# GEARDRONE_LITE.net
KiCad netlist of a schematic drawn in Altium Designer
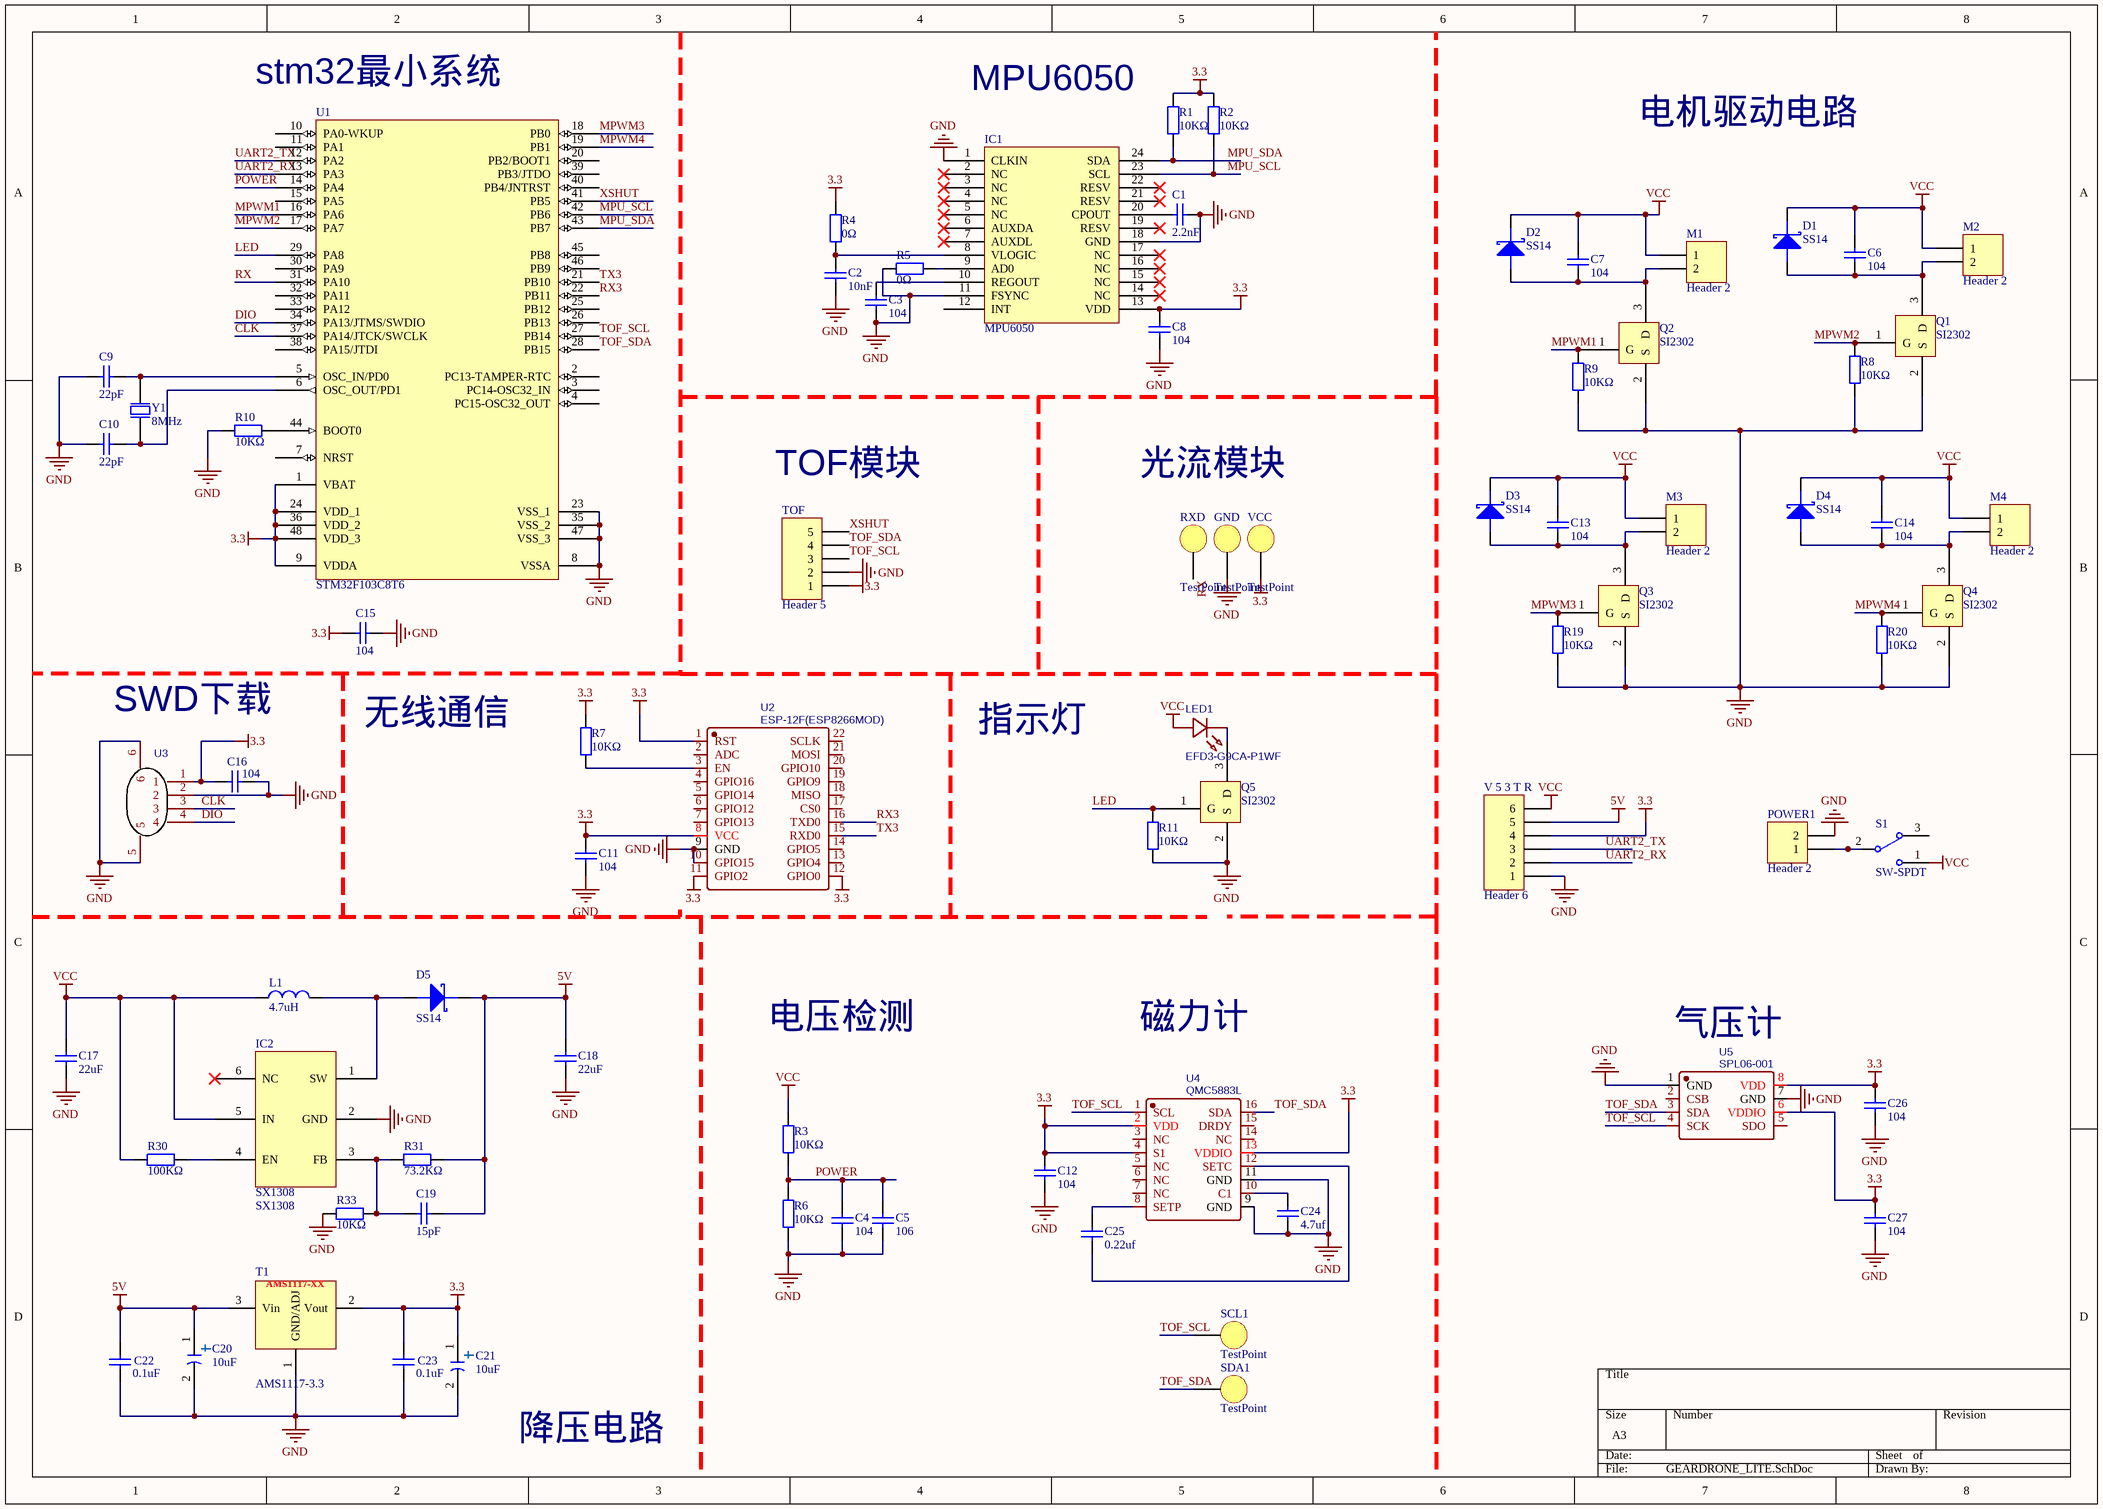
[diagram p0: GEARDRONE_LITE.SchDoc]

(export (version "E")
  (design (tool "Eeschema 10.0.6"))
  (components
    (comp (ref "C1")
      (value "2.2nF")
      (footprint "C0603")
      (description "Polarized Capacitor (Radial)")
      (fields (field (name "Comment") "2.2nf") (field (name "PUBLISHER") "Altium Limited"))
      (libsource (lib "电容") (part "Cap Chip 0603"))
    )
    (comp (ref "C2")
      (value "10nF")
      (footprint "C0603")
      (description "Polarized Capacitor (Radial)")
      (fields (field (name "Comment") "10nf") (field (name "PUBLISHER") "Altium Limited"))
      (libsource (lib "电容") (part "Cap Chip 0603"))
    )
    (comp (ref "C3")
      (value "104")
      (footprint "C0603")
      (description "Polarized Capacitor (Radial)")
      (fields (field (name "PUBLISHER") "Altium Limited"))
      (libsource (lib "电容") (part "Cap Chip 0603"))
    )
    (comp (ref "C4")
      (value "104")
      (footprint "C0603")
      (description "Polarized Capacitor (Radial)")
      (fields (field (name "PUBLISHER") "Altium Limited"))
      (libsource (lib "电容") (part "Cap Chip 0603"))
    )
    (comp (ref "C5")
      (value "106")
      (footprint "C0603")
      (description "Polarized Capacitor (Radial)")
      (fields (field (name "PUBLISHER") "Altium Limited"))
      (libsource (lib "电容") (part "Cap Chip 0603"))
    )
    (comp (ref "C6")
      (value "104")
      (footprint "C0603")
      (description "Polarized Capacitor (Radial)")
      (fields (field (name "PUBLISHER") "Altium Limited"))
      (libsource (lib "电容") (part "Cap Chip 0603"))
    )
    (comp (ref "C7")
      (value "104")
      (footprint "C0603")
      (description "Polarized Capacitor (Radial)")
      (fields (field (name "PUBLISHER") "Altium Limited"))
      (libsource (lib "电容") (part "Cap Chip 0603"))
    )
    (comp (ref "C8")
      (value "104")
      (footprint "C0603")
      (description "Polarized Capacitor (Radial)")
      (fields (field (name "PUBLISHER") "Altium Limited"))
      (libsource (lib "电容") (part "Cap Chip 0603"))
    )
    (comp (ref "C9")
      (value "22pF")
      (footprint "C0603")
      (description "Polarized Capacitor (Radial)")
      (fields (field (name "Comment") "20pf") (field (name "PUBLISHER") "Altium Limited"))
      (libsource (lib "电容") (part "Cap Chip 0805"))
    )
    (comp (ref "C10")
      (value "22pF")
      (footprint "C0603")
      (description "Polarized Capacitor (Radial)")
      (fields (field (name "PUBLISHER") "Altium Limited"))
      (libsource (lib "电容") (part "Cap Chip 0805"))
    )
    (comp (ref "C11")
      (value "104")
      (footprint "0603_C")
      (description "Polarized Capacitor (Radial)")
      (fields (field (name "PUBLISHER") "Altium Limited"))
      (libsource (lib "电容") (part "Cap Chip 0603"))
    )
    (comp (ref "C12")
      (value "104")
      (footprint "0603_C")
      (description "Polarized Capacitor (Radial)")
      (fields (field (name "PUBLISHER") "Altium Limited"))
      (libsource (lib "电容") (part "Cap Chip 0603"))
    )
    (comp (ref "C13")
      (value "104")
      (footprint "C0603")
      (description "Polarized Capacitor (Radial)")
      (fields (field (name "PUBLISHER") "Altium Limited"))
      (libsource (lib "电容") (part "Cap Chip 0603"))
    )
    (comp (ref "C14")
      (value "104")
      (footprint "C0603")
      (description "Polarized Capacitor (Radial)")
      (fields (field (name "PUBLISHER") "Altium Limited"))
      (libsource (lib "电容") (part "Cap Chip 0603"))
    )
    (comp (ref "C15")
      (value "104")
      (footprint "C0603")
      (description "Polarized Capacitor (Radial)")
      (fields (field (name "PUBLISHER") "Altium Limited"))
      (libsource (lib "电容") (part "Cap Chip 0603"))
    )
    (comp (ref "C16")
      (value "104")
      (footprint "C0603")
      (description "Polarized Capacitor (Radial)")
      (fields (field (name "PUBLISHER") "Altium Limited"))
      (libsource (lib "电容") (part "Cap Chip 0603"))
    )
    (comp (ref "C17")
      (value "22uF")
      (footprint "C0603")
      (description "Polarized Capacitor (Radial)")
      (fields (field (name "Comment") "22uf") (field (name "PUBLISHER") "Altium Limited"))
      (libsource (lib "电容") (part "Cap Chip 0603"))
    )
    (comp (ref "C18")
      (value "22uF")
      (footprint "C0603")
      (description "Polarized Capacitor (Radial)")
      (fields (field (name "Comment") "22uf") (field (name "PUBLISHER") "Altium Limited"))
      (libsource (lib "电容") (part "Cap Chip 0603"))
    )
    (comp (ref "C19")
      (value "15pF")
      (footprint "C0603")
      (description "Polarized Capacitor (Radial)")
      (fields (field (name "Comment") "15pf") (field (name "PUBLISHER") "Altium Limited"))
      (libsource (lib "电容") (part "Cap Chip 0603"))
    )
    (comp (ref "C20")
      (value "ECAP")
      (footprint "TAN-A-3216")
      (fields (field (name "ALTIUM_UNNAMED_1") "10uF"))
      (libsource (lib "mySchlib") (part "ECAP"))
    )
    (comp (ref "C21")
      (value "ECAP")
      (footprint "TAN-A-3216")
      (fields (field (name "ALTIUM_UNNAMED_1") "10uF"))
      (libsource (lib "mySchlib") (part "ECAP"))
    )
    (comp (ref "C22")
      (value "0.1uF")
      (footprint "C0603")
      (description "Polarized Capacitor (Radial)")
      (fields (field (name "Comment") "0.1uf") (field (name "PUBLISHER") "Altium Limited"))
      (libsource (lib "电容") (part "Cap Chip 0603"))
    )
    (comp (ref "C23")
      (value "0.1uF")
      (footprint "C0603")
      (description "Polarized Capacitor (Radial)")
      (fields (field (name "Comment") "0.1uf") (field (name "PUBLISHER") "Altium Limited"))
      (libsource (lib "电容") (part "Cap Chip 0603"))
    )
    (comp (ref "C24")
      (value "4.7uf")
      (footprint "0603_C")
      (description "Polarized Capacitor (Radial)")
      (fields (field (name "PUBLISHER") "Altium Limited"))
      (libsource (lib "电容") (part "Cap Chip 0603"))
    )
    (comp (ref "C25")
      (value "0.22uf")
      (footprint "0603_C")
      (description "Polarized Capacitor (Radial)")
      (fields (field (name "PUBLISHER") "Altium Limited"))
      (libsource (lib "电容") (part "Cap Chip 0603"))
    )
    (comp (ref "C26")
      (value "104")
      (footprint "0603_C")
      (description "Polarized Capacitor (Radial)")
      (fields (field (name "PUBLISHER") "Altium Limited"))
      (libsource (lib "电容") (part "Cap Chip 0603"))
    )
    (comp (ref "C27")
      (value "104")
      (footprint "0603_C")
      (description "Polarized Capacitor (Radial)")
      (fields (field (name "PUBLISHER") "Altium Limited"))
      (libsource (lib "电容") (part "Cap Chip 0603"))
    )
    (comp (ref "D1") (value "SS14") (footprint "SOD-323") (libsource (lib "二极管 三极管 MOS") (part "DIODE-TVS")))
    (comp (ref "D2") (value "SS14") (footprint "SOD-323") (libsource (lib "二极管 三极管 MOS") (part "DIODE-TVS")))
    (comp (ref "D3") (value "SS14") (footprint "SOD-323") (libsource (lib "二极管 三极管 MOS") (part "DIODE-TVS")))
    (comp (ref "D4") (value "SS14") (footprint "SOD-323") (libsource (lib "二极管 三极管 MOS") (part "DIODE-TVS")))
    (comp (ref "D5") (value "SS14") (footprint "SOD-323") (libsource (lib "二极管 三极管 MOS") (part "DIODE-TVS")))
    (comp (ref "GND")
      (value "TestPoint")
      (footprint "TestPoint")
      (libsource (lib "CQL_SchLib") (part "TestPoint"))
    )
    (comp (ref "IC1")
      (value "MPU6050")
      (footprint "LC-QFN-24_4x4x05P")
      (description "三轴陀螺仪")
      (libsource (lib "模块") (part "MPU6050"))
    )
    (comp (ref "IC2") (value "SX1308") (footprint "LC-SOT-23-6") (libsource (lib "Schlib1") (part "SX1308")))
    (comp (ref "L1")
      (value "4.7uH")
      (footprint "CD43NP")
      (description "Inductor")
      (fields (field (name "PUBLISHER") "Altium Limited"))
      (libsource (lib "电感磁珠共轭圈") (part "Inductor Chip"))
    )
    (comp (ref "LED1")
      (value "EFD3-G9CA-P1WF")
      (footprint "LED3528")
      (fields (field (name "BOM_SUPPLIER PART") "C507038") (field (name "CONTRIBUTOR") "LCSC"))
      (libsource (lib "altium-import") (part "root_2_EFD3-G9CA-P1WF_"))
    )
    (comp (ref "M1")
      (value "Header 2")
      (footprint "HDR1X2")
      (description "Header, 2-Pin")
      (fields (field (name "PUBLISHER") "Altium Limited"))
      (libsource (lib "The BeatlesIntegratedLibrary") (part "Header 2"))
    )
    (comp (ref "M2")
      (value "Header 2")
      (footprint "HDR1X2")
      (description "Header, 2-Pin")
      (fields (field (name "PUBLISHER") "Altium Limited"))
      (libsource (lib "The BeatlesIntegratedLibrary") (part "Header 2"))
    )
    (comp (ref "M3")
      (value "Header 2")
      (footprint "HDR1X2")
      (description "Header, 2-Pin")
      (fields (field (name "PUBLISHER") "Altium Limited"))
      (libsource (lib "The BeatlesIntegratedLibrary") (part "Header 2"))
    )
    (comp (ref "M4")
      (value "Header 2")
      (footprint "HDR1X2")
      (description "Header, 2-Pin")
      (fields (field (name "PUBLISHER") "Altium Limited"))
      (libsource (lib "The BeatlesIntegratedLibrary") (part "Header 2"))
    )
    (comp (ref "POWER1")
      (value "Header 2")
      (footprint "HDR1X2")
      (description "Header, 2-Pin")
      (fields (field (name "PUBLISHER") "Altium Limited"))
      (libsource (lib "") (part "Header 2_1"))
    )
    (comp (ref "Q1")
      (value "SI2302")
      (footprint "LC-SOT-23(SOT-23-3)")
      (libsource (lib "SI2302") (part "HANDSOME-SI2302-N"))
    )
    (comp (ref "Q2")
      (value "SI2302")
      (footprint "LC-SOT-23(SOT-23-3)")
      (libsource (lib "SI2302") (part "HANDSOME-SI2302-N"))
    )
    (comp (ref "Q3")
      (value "SI2302")
      (footprint "LC-SOT-23(SOT-23-3)")
      (libsource (lib "SI2302") (part "HANDSOME-SI2302-N"))
    )
    (comp (ref "Q4")
      (value "SI2302")
      (footprint "LC-SOT-23(SOT-23-3)")
      (libsource (lib "SI2302") (part "HANDSOME-SI2302-N"))
    )
    (comp (ref "Q5")
      (value "SI2302")
      (footprint "LC-SOT-23(SOT-23-3)")
      (libsource (lib "SI2302") (part "HANDSOME-SI2302-N"))
    )
    (comp (ref "R1")
      (value "10KΩ")
      (footprint "R0603")
      (description "Resistor")
      (fields (field (name "Comment") "10k") (field (name "PUBLISHER") "Altium Limited"))
      (libsource (lib "电阻") (part "Resistor Chip 0805"))
    )
    (comp (ref "R2")
      (value "10KΩ")
      (footprint "R0603")
      (description "Resistor")
      (fields (field (name "Comment") "10k") (field (name "PUBLISHER") "Altium Limited"))
      (libsource (lib "电阻") (part "Resistor Chip 0805"))
    )
    (comp (ref "R3")
      (value "10KΩ")
      (footprint "R0603")
      (description "Resistor")
      (fields (field (name "Comment") "10k") (field (name "PUBLISHER") "Altium Limited"))
      (libsource (lib "电阻") (part "Resistor Chip 0805"))
    )
    (comp (ref "R4")
      (value "0Ω")
      (footprint "R0603")
      (description "Resistor")
      (fields (field (name "Comment") "0") (field (name "PUBLISHER") "Altium Limited"))
      (libsource (lib "") (part "Resistor Chip 0805_3"))
    )
    (comp (ref "R5")
      (value "0Ω")
      (footprint "R0603")
      (description "Resistor")
      (fields (field (name "Comment") "0") (field (name "PUBLISHER") "Altium Limited"))
      (libsource (lib "") (part "Resistor Chip 0805_1"))
    )
    (comp (ref "R6")
      (value "10KΩ")
      (footprint "R0603")
      (description "Resistor")
      (fields (field (name "Comment") "10k") (field (name "PUBLISHER") "Altium Limited"))
      (libsource (lib "电阻") (part "Resistor Chip 0805"))
    )
    (comp (ref "R7")
      (value "10KΩ")
      (footprint "0603_R")
      (description "Resistor")
      (fields (field (name "Comment") "10k") (field (name "PUBLISHER") "Altium Limited"))
      (libsource (lib "电阻") (part "Resistor Chip 0805"))
    )
    (comp (ref "R8")
      (value "10KΩ")
      (footprint "R0603")
      (description "Resistor")
      (fields (field (name "Comment") "10k") (field (name "PUBLISHER") "Altium Limited"))
      (libsource (lib "电阻") (part "Resistor Chip 0805"))
    )
    (comp (ref "R9")
      (value "10KΩ")
      (footprint "R0603")
      (description "Resistor")
      (fields (field (name "Comment") "10k") (field (name "PUBLISHER") "Altium Limited"))
      (libsource (lib "") (part "Resistor Chip 0805_3"))
    )
    (comp (ref "R10")
      (value "10KΩ")
      (footprint "R0603")
      (description "Resistor")
      (fields (field (name "Comment") "10kΩ") (field (name "PUBLISHER") "Altium Limited"))
      (libsource (lib "") (part "Resistor Chip 0805_1"))
    )
    (comp (ref "R11")
      (value "10KΩ")
      (footprint "0603_R")
      (description "Resistor")
      (fields (field (name "Comment") "10k") (field (name "PUBLISHER") "Altium Limited"))
      (libsource (lib "") (part "Resistor Chip 0805_3"))
    )
    (comp (ref "R19")
      (value "10KΩ")
      (footprint "R0603")
      (description "Resistor")
      (fields (field (name "Comment") "10k") (field (name "PUBLISHER") "Altium Limited"))
      (libsource (lib "电阻") (part "Resistor Chip 0805"))
    )
    (comp (ref "R20")
      (value "10KΩ")
      (footprint "R0603")
      (description "Resistor")
      (fields (field (name "Comment") "10k") (field (name "PUBLISHER") "Altium Limited"))
      (libsource (lib "电阻") (part "Resistor Chip 0805"))
    )
    (comp (ref "R30")
      (value "100KΩ")
      (footprint "R0603")
      (description "Resistor")
      (fields (field (name "Comment") "100k") (field (name "PUBLISHER") "Altium Limited"))
      (libsource (lib "") (part "Resistor Chip 0805_1"))
    )
    (comp (ref "R31")
      (value "73.2KΩ")
      (footprint "R0603")
      (description "Resistor")
      (fields (field (name "Comment") "73.2k") (field (name "PUBLISHER") "Altium Limited"))
      (libsource (lib "") (part "Resistor Chip 0805_1"))
    )
    (comp (ref "R33")
      (value "10KΩ")
      (footprint "R0603")
      (description "Resistor")
      (fields (field (name "Comment") "10k") (field (name "PUBLISHER") "Altium Limited"))
      (libsource (lib "") (part "Resistor Chip 0805_2"))
    )
    (comp (ref "RXD")
      (value "TestPoint")
      (footprint "TestPoint")
      (libsource (lib "CQL_SchLib") (part "TestPoint"))
    )
    (comp (ref "S1")
      (value "SW-SPDT")
      (footprint "SW-TH_SS-12D10L5")
      (description "SPDT Subminiature Toggle Switch, Right Angle Mounting, Vertical Actuation")
      (fields (field (name "PUBLISHER") "Altium Limited"))
      (libsource (lib "开关按键器件") (part "SW-SPDT"))
    )
    (comp (ref "SCL1")
      (value "TestPoint")
      (footprint "TestPoint")
      (libsource (lib "CQL_SchLib") (part "TestPoint"))
    )
    (comp (ref "SDA1")
      (value "TestPoint")
      (footprint "TestPoint")
      (libsource (lib "CQL_SchLib") (part "TestPoint"))
    )
    (comp (ref "T1")
      (value "AMS1117-3.3")
      (footprint "SOT230P700X180-4N-LM2940")
      (description "AMS   800mA LOW DROPOUT VOLTAGE REGULATOR")
      (libsource (lib "电源ICs") (part "AMS1117-XX"))
    )
    (comp (ref "TOF")
      (value "Header 5")
      (footprint "HDR1X5")
      (description "Header, 5-Pin")
      (fields (field (name "PUBLISHER") "Altium Limited"))
      (libsource (lib "Miscellaneous Connectors") (part "Header 5"))
    )
    (comp (ref "U1")
      (value "STM32F103C8T6")
      (footprint "LC-LQFP-48_7x7x05P")
      (description "STM32 ARM-based 32-bit MCU with 64 Kbytes Flash, 48-pin LQFP, Industrial Temperature")
      (fields (field (name "PUBLISHER") "*"))
      (libsource (lib "ST MCU元件库") (part "STM32F103C8T6"))
    )
    (comp (ref "U2")
      (value "ESP-12F(ESP8266MOD)")
      (footprint "WIFIM-SMD_ESP-12F-ESP8266MOD")
      (fields (field (name "BOM_SUPPLIER PART") "C82891"))
      (libsource (lib "altium-import") (part "root_0_ESP-12F(ESP8266MOD)_"))
    )
    (comp (ref "U3")
      (value "SM04B-GHS-TB(LF)(SN)")
      (footprint "CONN-SMD_4P-P1.25_SM04B-GHS-TB-LF-SN")
      (fields (field (name "BOM_SUPPLIER PART") "C189895") (field (name "CONTRIBUTOR") "LCSC"))
      (libsource (lib "Y1") (part "SM04B-GHS-TB(LF)(SN)"))
    )
    (comp (ref "U4")
      (value "QMC5883L")
      (footprint "LPCC-16_L3.0-W3.0-P0.50-BL")
      (fields
        (field (name "BOM_SUPPLIER PART") "C2859540")
        (field (name "BOM_MANUFACTURER PART") "HMC5883L")
        (field (name "CONTRIBUTOR") "LCSC")
      )
      (libsource (lib "altium-import") (part "root_0_HMC5883L_"))
    )
    (comp (ref "U5")
      (value "SPL06-001")
      (footprint "SENSOR-SMD_SPL06-001")
      (fields (field (name "BOM_SUPPLIER PART") "C2684428") (field (name "CONTRIBUTOR") "LCSC"))
      (libsource (lib "altium-import") (part "root_0_SPL06-001_"))
    )
    (comp (ref "V 5 3 T R")
      (value "Header 6")
      (footprint "HDR1X6")
      (description "Header, 6-Pin")
      (fields (field (name "PUBLISHER") "Altium Limited"))
      (libsource (lib "Miscellaneous Connectors") (part "Header 6"))
    )
    (comp (ref "VCC")
      (value "TestPoint")
      (footprint "TestPoint")
      (libsource (lib "CQL_SchLib") (part "TestPoint"))
    )
    (comp (ref "Y1")
      (value "5032")
      (footprint "SMD5032-2")
      (description "Crystal Oscillator")
      (fields (field (name "FREQUENCY") "8MHz") (field (name "PUBLISHER") "Altium Limited"))
      (libsource (lib "蜂鸣器 咪头 保险丝 电池 晶振") (part "XTAL"))
    )
  )
  (nets
    (net (code "1") (name "/CLK") (class "Default")
      (node (ref "U1") (pin "37") (pinfunction "PA14/JTCK/SWCLK_37") (pintype "bidirectional"))
      (node (ref "U3") (pin "3") (pinfunction "3_3") (pintype "passive"))
    )
    (net (code "2") (name "/DIO") (class "Default")
      (node (ref "U1") (pin "34") (pinfunction "PA13/JTMS/SWDIO_34") (pintype "bidirectional"))
      (node (ref "U3") (pin "4") (pinfunction "4_4") (pintype "passive"))
    )
    (net (code "3") (name "/LED") (class "Default")
      (node (ref "Q5") (pin "1") (pinfunction "G_1") (pintype "passive"))
      (node (ref "R11") (pin "2") (pinfunction "2_2") (pintype "passive"))
      (node (ref "U1") (pin "29") (pinfunction "PA8_29") (pintype "bidirectional"))
    )
    (net (code "4") (name "/MPU_SCL") (class "Default")
      (node (ref "IC1") (pin "23") (pinfunction "SCL_23") (pintype "passive"))
      (node (ref "R2") (pin "2") (pinfunction "2_2") (pintype "passive"))
      (node (ref "U1") (pin "42") (pinfunction "PB6_42") (pintype "bidirectional"))
    )
    (net (code "5") (name "/MPU_SDA") (class "Default")
      (node (ref "IC1") (pin "24") (pinfunction "SDA_24") (pintype "passive"))
      (node (ref "R1") (pin "2") (pinfunction "2_2") (pintype "passive"))
      (node (ref "U1") (pin "43") (pinfunction "PB7_43") (pintype "bidirectional"))
    )
    (net (code "6") (name "/MPWM1") (class "Default")
      (node (ref "Q2") (pin "1") (pinfunction "G_1") (pintype "passive"))
      (node (ref "R9") (pin "2") (pinfunction "2_2") (pintype "passive"))
      (node (ref "U1") (pin "16") (pinfunction "PA6_16") (pintype "bidirectional"))
    )
    (net (code "7") (name "/MPWM2") (class "Default")
      (node (ref "Q1") (pin "1") (pinfunction "G_1") (pintype "passive"))
      (node (ref "R8") (pin "1") (pinfunction "1_1") (pintype "passive"))
      (node (ref "U1") (pin "17") (pinfunction "PA7_17") (pintype "bidirectional"))
    )
    (net (code "8") (name "/MPWM3") (class "Default")
      (node (ref "Q3") (pin "1") (pinfunction "G_1") (pintype "passive"))
      (node (ref "R19") (pin "1") (pinfunction "1_1") (pintype "passive"))
      (node (ref "U1") (pin "18") (pinfunction "PB0_18") (pintype "bidirectional"))
    )
    (net (code "9") (name "/MPWM4") (class "Default")
      (node (ref "Q4") (pin "1") (pinfunction "G_1") (pintype "passive"))
      (node (ref "R20") (pin "1") (pinfunction "1_1") (pintype "passive"))
      (node (ref "U1") (pin "19") (pinfunction "PB1_19") (pintype "bidirectional"))
    )
    (net (code "10") (name "/POWER") (class "Default")
      (node (ref "C4") (pin "1") (pinfunction "1_1") (pintype "passive"))
      (node (ref "C5") (pin "1") (pinfunction "1_1") (pintype "passive"))
      (node (ref "R3") (pin "2") (pinfunction "2_2") (pintype "passive"))
      (node (ref "R6") (pin "1") (pinfunction "1_1") (pintype "passive"))
      (node (ref "U1") (pin "14") (pinfunction "PA4_14") (pintype "bidirectional"))
    )
    (net (code "11") (name "/RX") (class "Default")
      (node (ref "RXD") (pin "1") (pinfunction "TestPoint_1") (pintype "passive"))
      (node (ref "U1") (pin "31") (pinfunction "PA10_31") (pintype "bidirectional"))
    )
    (net (code "12") (name "/RX3") (class "Default")
      (node (ref "U1") (pin "22") (pinfunction "PB11_22") (pintype "bidirectional"))
      (node (ref "U2") (pin "16") (pinfunction "TXD0_16") (pintype "passive"))
    )
    (net (code "13") (name "/TOF_SCL") (class "Default")
      (node (ref "SCL1") (pin "1") (pinfunction "TestPoint_1") (pintype "passive"))
      (node (ref "TOF") (pin "3") (pinfunction "3_3") (pintype "passive"))
      (node (ref "U1") (pin "27") (pinfunction "PB14_27") (pintype "bidirectional"))
      (node (ref "U4") (pin "1") (pinfunction "SCL_1") (pintype "passive"))
      (node (ref "U5") (pin "4") (pinfunction "SCK_4") (pintype "passive"))
    )
    (net (code "14") (name "/TOF_SDA") (class "Default")
      (node (ref "SDA1") (pin "1") (pinfunction "TestPoint_1") (pintype "passive"))
      (node (ref "TOF") (pin "4") (pinfunction "4_4") (pintype "passive"))
      (node (ref "U1") (pin "28") (pinfunction "PB15_28") (pintype "bidirectional"))
      (node (ref "U4") (pin "16") (pinfunction "SDA_16") (pintype "passive"))
      (node (ref "U5") (pin "3") (pinfunction "SDA_3") (pintype "passive"))
    )
    (net (code "15") (name "/TX3") (class "Default")
      (node (ref "U1") (pin "21") (pinfunction "PB10_21") (pintype "bidirectional"))
      (node (ref "U2") (pin "15") (pinfunction "RXD0_15") (pintype "passive"))
    )
    (net (code "16") (name "/UART2_RX") (class "Default")
      (node (ref "U1") (pin "13") (pinfunction "PA3_13") (pintype "bidirectional"))
      (node (ref "V 5 3 T R") (pin "2") (pinfunction "2_2") (pintype "passive"))
    )
    (net (code "17") (name "/UART2_TX") (class "Default")
      (node (ref "U1") (pin "12") (pinfunction "PA2_12") (pintype "bidirectional"))
      (node (ref "V 5 3 T R") (pin "3") (pinfunction "3_3") (pintype "passive"))
    )
    (net (code "18") (name "/XSHUT") (class "Default")
      (node (ref "TOF") (pin "5") (pinfunction "5_5") (pintype "passive"))
      (node (ref "U1") (pin "41") (pinfunction "PB5_41") (pintype "bidirectional"))
    )
    (net (code "19") (name "3.3") (class "Default")
      (node (ref "C11") (pin "1") (pinfunction "1_1") (pintype "passive"))
      (node (ref "C12") (pin "1") (pinfunction "1_1") (pintype "passive"))
      (node (ref "C15") (pin "2") (pinfunction "2_2") (pintype "passive"))
      (node (ref "C16") (pin "2") (pinfunction "2_2") (pintype "passive"))
      (node (ref "C21") (pin "1") (pinfunction "1_1") (pintype "passive"))
      (node (ref "C23") (pin "2") (pinfunction "2_2") (pintype "passive"))
      (node (ref "C26") (pin "1") (pinfunction "1_1") (pintype "passive"))
      (node (ref "C27") (pin "1") (pinfunction "1_1") (pintype "passive"))
      (node (ref "C8") (pin "1") (pinfunction "1_1") (pintype "passive"))
      (node (ref "IC1") (pin "13") (pinfunction "VDD_13") (pintype "passive"))
      (node (ref "R1") (pin "1") (pinfunction "1_1") (pintype "passive"))
      (node (ref "R2") (pin "1") (pinfunction "1_1") (pintype "passive"))
      (node (ref "R4") (pin "2") (pinfunction "2_2") (pintype "passive"))
      (node (ref "R7") (pin "1") (pinfunction "1_1") (pintype "passive"))
      (node (ref "T1") (pin "2") (pinfunction "Vout_2") (pintype "passive"))
      (node (ref "TOF") (pin "1") (pinfunction "1_1") (pintype "passive"))
      (node (ref "U1") (pin "1") (pinfunction "VBAT_1") (pintype "power_in"))
      (node (ref "U1") (pin "24") (pinfunction "VDD_1_24") (pintype "power_in"))
      (node (ref "U1") (pin "36") (pinfunction "VDD_2_36") (pintype "power_in"))
      (node (ref "U1") (pin "48") (pinfunction "VDD_3_48") (pintype "power_in"))
      (node (ref "U1") (pin "9") (pinfunction "VDDA_9") (pintype "power_in"))
      (node (ref "U2") (pin "1") (pinfunction "RST_1") (pintype "passive"))
      (node (ref "U2") (pin "11") (pinfunction "GPIO2_11") (pintype "passive"))
      (node (ref "U2") (pin "12") (pinfunction "GPIO0_12") (pintype "passive"))
      (node (ref "U2") (pin "8") (pinfunction "VCC_8") (pintype "passive"))
      (node (ref "U3") (pin "1") (pinfunction "1_1") (pintype "passive"))
      (node (ref "U4") (pin "13") (pinfunction "VDDIO_13") (pintype "passive"))
      (node (ref "U4") (pin "2") (pinfunction "VDD_2") (pintype "passive"))
      (node (ref "U4") (pin "4") (pinfunction "S1_4") (pintype "passive"))
      (node (ref "U5") (pin "6") (pinfunction "VDDIO_6") (pintype "passive"))
      (node (ref "U5") (pin "8") (pinfunction "VDD_8") (pintype "passive"))
      (node (ref "V 5 3 T R") (pin "4") (pinfunction "4_4") (pintype "passive"))
      (node (ref "VCC") (pin "1") (pinfunction "TestPoint_1") (pintype "passive"))
    )
    (net (code "20") (name "5V") (class "Default")
      (node (ref "C18") (pin "2") (pinfunction "2_2") (pintype "passive"))
      (node (ref "C19") (pin "1") (pinfunction "1_1") (pintype "passive"))
      (node (ref "C20") (pin "1") (pinfunction "1_1") (pintype "passive"))
      (node (ref "C22") (pin "2") (pinfunction "2_2") (pintype "passive"))
      (node (ref "D5") (pin "2") (pinfunction "K_2") (pintype "passive"))
      (node (ref "R31") (pin "2") (pinfunction "2_2") (pintype "passive"))
      (node (ref "T1") (pin "3") (pinfunction "Vin_3") (pintype "passive"))
      (node (ref "V 5 3 T R") (pin "5") (pinfunction "5_5") (pintype "passive"))
    )
    (net (code "21") (name "GND") (class "Default")
      (node (ref "C1") (pin "2") (pinfunction "2_2") (pintype "passive"))
      (node (ref "C10") (pin "1") (pinfunction "1_1") (pintype "passive"))
      (node (ref "C11") (pin "2") (pinfunction "2_2") (pintype "passive"))
      (node (ref "C12") (pin "2") (pinfunction "2_2") (pintype "passive"))
      (node (ref "C15") (pin "1") (pinfunction "1_1") (pintype "passive"))
      (node (ref "C16") (pin "1") (pinfunction "1_1") (pintype "passive"))
      (node (ref "C17") (pin "1") (pinfunction "1_1") (pintype "passive"))
      (node (ref "C18") (pin "1") (pinfunction "1_1") (pintype "passive"))
      (node (ref "C2") (pin "1") (pinfunction "1_1") (pintype "passive"))
      (node (ref "C20") (pin "2") (pinfunction "2_2") (pintype "passive"))
      (node (ref "C21") (pin "2") (pinfunction "2_2") (pintype "passive"))
      (node (ref "C22") (pin "1") (pinfunction "1_1") (pintype "passive"))
      (node (ref "C23") (pin "1") (pinfunction "1_1") (pintype "passive"))
      (node (ref "C24") (pin "1") (pinfunction "1_1") (pintype "passive"))
      (node (ref "C26") (pin "2") (pinfunction "2_2") (pintype "passive"))
      (node (ref "C27") (pin "2") (pinfunction "2_2") (pintype "passive"))
      (node (ref "C3") (pin "2") (pinfunction "2_2") (pintype "passive"))
      (node (ref "C4") (pin "2") (pinfunction "2_2") (pintype "passive"))
      (node (ref "C5") (pin "2") (pinfunction "2_2") (pintype "passive"))
      (node (ref "C8") (pin "2") (pinfunction "2_2") (pintype "passive"))
      (node (ref "C9") (pin "1") (pinfunction "1_1") (pintype "passive"))
      (node (ref "GND") (pin "1") (pinfunction "TestPoint_1") (pintype "passive"))
      (node (ref "IC1") (pin "1") (pinfunction "CLKIN_1") (pintype "passive"))
      (node (ref "IC1") (pin "11") (pinfunction "FSYNC_11") (pintype "passive"))
      (node (ref "IC1") (pin "18") (pinfunction "GND_18") (pintype "passive"))
      (node (ref "IC2") (pin "2") (pinfunction "GND_2") (pintype "passive"))
      (node (ref "POWER1") (pin "2") (pinfunction "2_2") (pintype "passive"))
      (node (ref "Q1") (pin "2") (pinfunction "S_2") (pintype "passive"))
      (node (ref "Q2") (pin "2") (pinfunction "S_2") (pintype "passive"))
      (node (ref "Q3") (pin "2") (pinfunction "S_2") (pintype "passive"))
      (node (ref "Q4") (pin "2") (pinfunction "S_2") (pintype "passive"))
      (node (ref "Q5") (pin "2") (pinfunction "S_2") (pintype "passive"))
      (node (ref "R10") (pin "1") (pinfunction "1_1") (pintype "passive"))
      (node (ref "R11") (pin "1") (pinfunction "1_1") (pintype "passive"))
      (node (ref "R19") (pin "2") (pinfunction "2_2") (pintype "passive"))
      (node (ref "R20") (pin "2") (pinfunction "2_2") (pintype "passive"))
      (node (ref "R33") (pin "2") (pinfunction "2_2") (pintype "passive"))
      (node (ref "R5") (pin "1") (pinfunction "1_1") (pintype "passive"))
      (node (ref "R6") (pin "2") (pinfunction "2_2") (pintype "passive"))
      (node (ref "R8") (pin "2") (pinfunction "2_2") (pintype "passive"))
      (node (ref "R9") (pin "1") (pinfunction "1_1") (pintype "passive"))
      (node (ref "T1") (pin "1") (pinfunction "GND/ADJ_1") (pintype "passive"))
      (node (ref "TOF") (pin "2") (pinfunction "2_2") (pintype "passive"))
      (node (ref "U1") (pin "23") (pinfunction "VSS_1_23") (pintype "power_in"))
      (node (ref "U1") (pin "35") (pinfunction "VSS_2_35") (pintype "power_in"))
      (node (ref "U1") (pin "47") (pinfunction "VSS_3_47") (pintype "power_in"))
      (node (ref "U1") (pin "8") (pinfunction "VSSA_8") (pintype "power_in"))
      (node (ref "U2") (pin "10") (pinfunction "GPIO15_10") (pintype "passive"))
      (node (ref "U2") (pin "9") (pinfunction "GND_9") (pintype "passive"))
      (node (ref "U3") (pin "2") (pinfunction "2_2") (pintype "passive"))
      (node (ref "U3") (pin "5") (pinfunction "5_5") (pintype "passive"))
      (node (ref "U3") (pin "6") (pinfunction "6_6") (pintype "passive"))
      (node (ref "U4") (pin "11") (pinfunction "GND_11") (pintype "passive"))
      (node (ref "U4") (pin "9") (pinfunction "GND_9") (pintype "passive"))
      (node (ref "U5") (pin "1") (pinfunction "GND_1") (pintype "passive"))
      (node (ref "U5") (pin "7") (pinfunction "GND_7") (pintype "passive"))
      (node (ref "V 5 3 T R") (pin "1") (pinfunction "1_1") (pintype "passive"))
    )
    (net (code "22") (name "Net-(D1-A)") (class "Default")
      (node (ref "C6") (pin "1") (pinfunction "1_1") (pintype "passive"))
      (node (ref "D1") (pin "1") (pinfunction "A_1") (pintype "passive"))
      (node (ref "M2") (pin "2") (pinfunction "2_2") (pintype "passive"))
      (node (ref "Q1") (pin "3") (pinfunction "D_3") (pintype "passive"))
    )
    (net (code "23") (name "Net-(D2-A)") (class "Default")
      (node (ref "C7") (pin "1") (pinfunction "1_1") (pintype "passive"))
      (node (ref "D2") (pin "1") (pinfunction "A_1") (pintype "passive"))
      (node (ref "M1") (pin "2") (pinfunction "2_2") (pintype "passive"))
      (node (ref "Q2") (pin "3") (pinfunction "D_3") (pintype "passive"))
    )
    (net (code "24") (name "Net-(D3-A)") (class "Default")
      (node (ref "C13") (pin "1") (pinfunction "1_1") (pintype "passive"))
      (node (ref "D3") (pin "1") (pinfunction "A_1") (pintype "passive"))
      (node (ref "M3") (pin "2") (pinfunction "2_2") (pintype "passive"))
      (node (ref "Q3") (pin "3") (pinfunction "D_3") (pintype "passive"))
    )
    (net (code "25") (name "Net-(D4-A)") (class "Default")
      (node (ref "C14") (pin "1") (pinfunction "1_1") (pintype "passive"))
      (node (ref "D4") (pin "1") (pinfunction "A_1") (pintype "passive"))
      (node (ref "M4") (pin "2") (pinfunction "2_2") (pintype "passive"))
      (node (ref "Q4") (pin "3") (pinfunction "D_3") (pintype "passive"))
    )
    (net (code "26") (name "Net-(D5-A)") (class "Default")
      (node (ref "D5") (pin "1") (pinfunction "A_1") (pintype "passive"))
      (node (ref "IC2") (pin "1") (pinfunction "SW_1") (pintype "passive"))
      (node (ref "L1") (pin "2") (pinfunction "2_2") (pintype "passive"))
    )
    (net (code "27") (name "Net-(IC1-AD0)") (class "Default")
      (node (ref "IC1") (pin "9") (pinfunction "AD0_9") (pintype "passive"))
      (node (ref "R5") (pin "2") (pinfunction "2_2") (pintype "passive"))
    )
    (net (code "28") (name "Net-(IC1-CPOUT)") (class "Default")
      (node (ref "C1") (pin "1") (pinfunction "1_1") (pintype "passive"))
      (node (ref "IC1") (pin "20") (pinfunction "CPOUT_20") (pintype "passive"))
    )
    (net (code "29") (name "Net-(IC1-REGOUT)") (class "Default")
      (node (ref "C3") (pin "1") (pinfunction "1_1") (pintype "passive"))
      (node (ref "IC1") (pin "10") (pinfunction "REGOUT_10") (pintype "passive"))
    )
    (net (code "30") (name "Net-(IC1-VLOGIC)") (class "Default")
      (node (ref "C2") (pin "2") (pinfunction "2_2") (pintype "passive"))
      (node (ref "IC1") (pin "8") (pinfunction "VLOGIC_8") (pintype "passive"))
      (node (ref "R4") (pin "1") (pinfunction "1_1") (pintype "passive"))
    )
    (net (code "31") (name "Net-(IC2-EN)") (class "Default")
      (node (ref "IC2") (pin "4") (pinfunction "EN_4") (pintype "passive"))
      (node (ref "R30") (pin "2") (pinfunction "2_2") (pintype "passive"))
    )
    (net (code "32") (name "Net-(IC2-FB)") (class "Default")
      (node (ref "C19") (pin "2") (pinfunction "2_2") (pintype "passive"))
      (node (ref "IC2") (pin "3") (pinfunction "FB_3") (pintype "passive"))
      (node (ref "R31") (pin "1") (pinfunction "1_1") (pintype "passive"))
      (node (ref "R33") (pin "1") (pinfunction "1_1") (pintype "passive"))
    )
    (net (code "33") (name "Net-(LED1-K)") (class "Default")
      (node (ref "LED1") (pin "1") (pinfunction "K_1") (pintype "passive"))
      (node (ref "Q5") (pin "3") (pinfunction "D_3") (pintype "passive"))
    )
    (net (code "34") (name "Net-(POWER1-Pad1)") (class "Default")
      (node (ref "POWER1") (pin "1") (pinfunction "1_1") (pintype "passive"))
      (node (ref "S1") (pin "2") (pintype "passive"))
    )
    (net (code "35") (name "Net-(U1-BOOT0)") (class "Default")
      (node (ref "R10") (pin "2") (pinfunction "2_2") (pintype "passive"))
      (node (ref "U1") (pin "44") (pinfunction "BOOT0_44") (pintype "input"))
    )
    (net (code "36") (name "Net-(U1-OSC_IN{slash}PD0)") (class "Default")
      (node (ref "C9") (pin "2") (pinfunction "2_2") (pintype "passive"))
      (node (ref "U1") (pin "5") (pinfunction "OSC_IN/PD0_5") (pintype "input"))
      (node (ref "Y1") (pin "2") (pinfunction "OSC2_2") (pintype "passive"))
    )
    (net (code "37") (name "Net-(U1-OSC_OUT{slash}PD1)") (class "Default")
      (node (ref "C10") (pin "2") (pinfunction "2_2") (pintype "passive"))
      (node (ref "U1") (pin "6") (pinfunction "OSC_OUT/PD1_6") (pintype "output"))
      (node (ref "Y1") (pin "1") (pinfunction "OSC1_1") (pintype "passive"))
    )
    (net (code "38") (name "Net-(U2-EN)") (class "Default")
      (node (ref "R7") (pin "2") (pinfunction "2_2") (pintype "passive"))
      (node (ref "U2") (pin "3") (pinfunction "EN_3") (pintype "passive"))
    )
    (net (code "39") (name "Net-(U4-C1)") (class "Default")
      (node (ref "C24") (pin "2") (pinfunction "2_2") (pintype "passive"))
      (node (ref "U4") (pin "10") (pinfunction "C1_10") (pintype "passive"))
    )
    (net (code "40") (name "Net-(U4-SETC)") (class "Default")
      (node (ref "C25") (pin "1") (pinfunction "1_1") (pintype "passive"))
      (node (ref "U4") (pin "12") (pinfunction "SETC_12") (pintype "passive"))
    )
    (net (code "41") (name "Net-(U4-SETP)") (class "Default")
      (node (ref "C25") (pin "2") (pinfunction "2_2") (pintype "passive"))
      (node (ref "U4") (pin "8") (pinfunction "SETP_8") (pintype "passive"))
    )
    (net (code "42") (name "VCC") (class "Default")
      (node (ref "C13") (pin "2") (pinfunction "2_2") (pintype "passive"))
      (node (ref "C14") (pin "2") (pinfunction "2_2") (pintype "passive"))
      (node (ref "C17") (pin "2") (pinfunction "2_2") (pintype "passive"))
      (node (ref "C6") (pin "2") (pinfunction "2_2") (pintype "passive"))
      (node (ref "C7") (pin "2") (pinfunction "2_2") (pintype "passive"))
      (node (ref "D1") (pin "2") (pinfunction "K_2") (pintype "passive"))
      (node (ref "D2") (pin "2") (pinfunction "K_2") (pintype "passive"))
      (node (ref "D3") (pin "2") (pinfunction "K_2") (pintype "passive"))
      (node (ref "D4") (pin "2") (pinfunction "K_2") (pintype "passive"))
      (node (ref "IC2") (pin "5") (pinfunction "IN_5") (pintype "passive"))
      (node (ref "L1") (pin "1") (pinfunction "1_1") (pintype "passive"))
      (node (ref "LED1") (pin "2") (pinfunction "A_2") (pintype "passive"))
      (node (ref "M1") (pin "1") (pinfunction "1_1") (pintype "passive"))
      (node (ref "M2") (pin "1") (pinfunction "1_1") (pintype "passive"))
      (node (ref "M3") (pin "1") (pinfunction "1_1") (pintype "passive"))
      (node (ref "M4") (pin "1") (pinfunction "1_1") (pintype "passive"))
      (node (ref "R3") (pin "1") (pinfunction "1_1") (pintype "passive"))
      (node (ref "R30") (pin "1") (pinfunction "1_1") (pintype "passive"))
      (node (ref "S1") (pin "1") (pintype "passive"))
      (node (ref "V 5 3 T R") (pin "6") (pinfunction "6_6") (pintype "passive"))
    )
    (net (code "43") (name "unconnected-(IC1-AUXDA-Pad6)") (class "Default")
      (node (ref "IC1") (pin "6") (pinfunction "AUXDA_6") (pintype "passive+no_connect"))
    )
    (net (code "44") (name "unconnected-(IC1-AUXDL-Pad7)") (class "Default")
      (node (ref "IC1") (pin "7") (pinfunction "AUXDL_7") (pintype "passive+no_connect"))
    )
    (net (code "45") (name "unconnected-(IC1-INT-Pad12)") (class "Default")
      (node (ref "IC1") (pin "12") (pinfunction "INT_12") (pintype "passive"))
    )
    (net (code "46") (name "unconnected-(IC1-NC-Pad2)") (class "Default")
      (node (ref "IC1") (pin "2") (pinfunction "NC_2") (pintype "passive+no_connect"))
    )
    (net (code "47") (name "unconnected-(IC1-NC-Pad3)") (class "Default")
      (node (ref "IC1") (pin "3") (pinfunction "NC_3") (pintype "passive+no_connect"))
    )
    (net (code "48") (name "unconnected-(IC1-NC-Pad4)") (class "Default")
      (node (ref "IC1") (pin "4") (pinfunction "NC_4") (pintype "passive+no_connect"))
    )
    (net (code "49") (name "unconnected-(IC1-NC-Pad5)") (class "Default")
      (node (ref "IC1") (pin "5") (pinfunction "NC_5") (pintype "passive+no_connect"))
    )
    (net (code "50") (name "unconnected-(IC1-NC-Pad14)") (class "Default")
      (node (ref "IC1") (pin "14") (pinfunction "NC_14") (pintype "passive+no_connect"))
    )
    (net (code "51") (name "unconnected-(IC1-NC-Pad15)") (class "Default")
      (node (ref "IC1") (pin "15") (pinfunction "NC_15") (pintype "passive+no_connect"))
    )
    (net (code "52") (name "unconnected-(IC1-NC-Pad16)") (class "Default")
      (node (ref "IC1") (pin "16") (pinfunction "NC_16") (pintype "passive+no_connect"))
    )
    (net (code "53") (name "unconnected-(IC1-NC-Pad17)") (class "Default")
      (node (ref "IC1") (pin "17") (pinfunction "NC_17") (pintype "passive+no_connect"))
    )
    (net (code "54") (name "unconnected-(IC1-RESV-Pad19)") (class "Default")
      (node (ref "IC1") (pin "19") (pinfunction "RESV_19") (pintype "passive+no_connect"))
    )
    (net (code "55") (name "unconnected-(IC1-RESV-Pad21)") (class "Default")
      (node (ref "IC1") (pin "21") (pinfunction "RESV_21") (pintype "passive+no_connect"))
    )
    (net (code "56") (name "unconnected-(IC1-RESV-Pad22)") (class "Default")
      (node (ref "IC1") (pin "22") (pinfunction "RESV_22") (pintype "passive+no_connect"))
    )
    (net (code "57") (name "unconnected-(IC2-NC-Pad6)") (class "Default")
      (node (ref "IC2") (pin "6") (pinfunction "NC_6") (pintype "passive+no_connect"))
    )
    (net (code "58") (name "unconnected-(S1-Pad3)") (class "Default")
      (node (ref "S1") (pin "3") (pintype "passive"))
    )
    (net (code "59") (name "unconnected-(U1-NRST-Pad7)") (class "Default")
      (node (ref "U1") (pin "7") (pinfunction "NRST_7") (pintype "bidirectional"))
    )
    (net (code "60") (name "unconnected-(U1-PA0-WKUP-Pad10)") (class "Default")
      (node (ref "U1") (pin "10") (pinfunction "PA0-WKUP_10") (pintype "bidirectional"))
    )
    (net (code "61") (name "unconnected-(U1-PA1-Pad11)") (class "Default")
      (node (ref "U1") (pin "11") (pinfunction "PA1_11") (pintype "bidirectional"))
    )
    (net (code "62") (name "unconnected-(U1-PA5-Pad15)") (class "Default")
      (node (ref "U1") (pin "15") (pinfunction "PA5_15") (pintype "bidirectional"))
    )
    (net (code "63") (name "unconnected-(U1-PA9-Pad30)") (class "Default")
      (node (ref "U1") (pin "30") (pinfunction "PA9_30") (pintype "bidirectional"))
    )
    (net (code "64") (name "unconnected-(U1-PA11-Pad32)") (class "Default")
      (node (ref "U1") (pin "32") (pinfunction "PA11_32") (pintype "bidirectional"))
    )
    (net (code "65") (name "unconnected-(U1-PA12-Pad33)") (class "Default")
      (node (ref "U1") (pin "33") (pinfunction "PA12_33") (pintype "bidirectional"))
    )
    (net (code "66") (name "unconnected-(U1-PA15{slash}JTDI-Pad38)") (class "Default")
      (node (ref "U1") (pin "38") (pinfunction "PA15/JTDI_38") (pintype "bidirectional"))
    )
    (net (code "67") (name "unconnected-(U1-PB2{slash}BOOT1-Pad20)") (class "Default")
      (node (ref "U1") (pin "20") (pinfunction "PB2/BOOT1_20") (pintype "bidirectional"))
    )
    (net (code "68") (name "unconnected-(U1-PB3{slash}JTDO-Pad39)") (class "Default")
      (node (ref "U1") (pin "39") (pinfunction "PB3/JTDO_39") (pintype "bidirectional"))
    )
    (net (code "69") (name "unconnected-(U1-PB4{slash}JNTRST-Pad40)") (class "Default")
      (node (ref "U1") (pin "40") (pinfunction "PB4/JNTRST_40") (pintype "bidirectional"))
    )
    (net (code "70") (name "unconnected-(U1-PB8-Pad45)") (class "Default")
      (node (ref "U1") (pin "45") (pinfunction "PB8_45") (pintype "bidirectional"))
    )
    (net (code "71") (name "unconnected-(U1-PB9-Pad46)") (class "Default")
      (node (ref "U1") (pin "46") (pinfunction "PB9_46") (pintype "bidirectional"))
    )
    (net (code "72") (name "unconnected-(U1-PB12-Pad25)") (class "Default")
      (node (ref "U1") (pin "25") (pinfunction "PB12_25") (pintype "bidirectional"))
    )
    (net (code "73") (name "unconnected-(U1-PB13-Pad26)") (class "Default")
      (node (ref "U1") (pin "26") (pinfunction "PB13_26") (pintype "bidirectional"))
    )
    (net (code "74") (name "unconnected-(U1-PC13-TAMPER-RTC-Pad2)") (class "Default")
      (node (ref "U1") (pin "2") (pinfunction "PC13-TAMPER-RTC_2") (pintype "bidirectional"))
    )
    (net (code "75") (name "unconnected-(U1-PC14-OSC32_IN-Pad3)") (class "Default")
      (node (ref "U1") (pin "3") (pinfunction "PC14-OSC32_IN_3") (pintype "bidirectional"))
    )
    (net (code "76") (name "unconnected-(U1-PC15-OSC32_OUT-Pad4)") (class "Default")
      (node (ref "U1") (pin "4") (pinfunction "PC15-OSC32_OUT_4") (pintype "bidirectional"))
    )
    (net (code "77") (name "unconnected-(U2-ADC-Pad2)") (class "Default")
      (node (ref "U2") (pin "2") (pinfunction "ADC_2") (pintype "passive"))
    )
    (net (code "78") (name "unconnected-(U2-CS0-Pad17)") (class "Default")
      (node (ref "U2") (pin "17") (pinfunction "CS0_17") (pintype "passive"))
    )
    (net (code "79") (name "unconnected-(U2-GPIO4-Pad13)") (class "Default")
      (node (ref "U2") (pin "13") (pinfunction "GPIO4_13") (pintype "passive"))
    )
    (net (code "80") (name "unconnected-(U2-GPIO5-Pad14)") (class "Default")
      (node (ref "U2") (pin "14") (pinfunction "GPIO5_14") (pintype "passive"))
    )
    (net (code "81") (name "unconnected-(U2-GPIO9-Pad19)") (class "Default")
      (node (ref "U2") (pin "19") (pinfunction "GPIO9_19") (pintype "passive"))
    )
    (net (code "82") (name "unconnected-(U2-GPIO10-Pad20)") (class "Default")
      (node (ref "U2") (pin "20") (pinfunction "GPIO10_20") (pintype "passive"))
    )
    (net (code "83") (name "unconnected-(U2-GPIO12-Pad6)") (class "Default")
      (node (ref "U2") (pin "6") (pinfunction "GPIO12_6") (pintype "passive"))
    )
    (net (code "84") (name "unconnected-(U2-GPIO13-Pad7)") (class "Default")
      (node (ref "U2") (pin "7") (pinfunction "GPIO13_7") (pintype "passive"))
    )
    (net (code "85") (name "unconnected-(U2-GPIO14-Pad5)") (class "Default")
      (node (ref "U2") (pin "5") (pinfunction "GPIO14_5") (pintype "passive"))
    )
    (net (code "86") (name "unconnected-(U2-GPIO16-Pad4)") (class "Default")
      (node (ref "U2") (pin "4") (pinfunction "GPIO16_4") (pintype "passive"))
    )
    (net (code "87") (name "unconnected-(U2-MISO-Pad18)") (class "Default")
      (node (ref "U2") (pin "18") (pinfunction "MISO_18") (pintype "passive"))
    )
    (net (code "88") (name "unconnected-(U2-MOSI-Pad21)") (class "Default")
      (node (ref "U2") (pin "21") (pinfunction "MOSI_21") (pintype "passive"))
    )
    (net (code "89") (name "unconnected-(U2-SCLK-Pad22)") (class "Default")
      (node (ref "U2") (pin "22") (pinfunction "SCLK_22") (pintype "passive"))
    )
    (net (code "90") (name "unconnected-(U4-DRDY-Pad15)") (class "Default")
      (node (ref "U4") (pin "15") (pinfunction "DRDY_15") (pintype "passive"))
    )
    (net (code "91") (name "unconnected-(U4-NC-Pad3)") (class "Default")
      (node (ref "U4") (pin "3") (pinfunction "NC_3") (pintype "passive"))
    )
    (net (code "92") (name "unconnected-(U4-NC-Pad5)") (class "Default")
      (node (ref "U4") (pin "5") (pinfunction "NC_5") (pintype "passive"))
    )
    (net (code "93") (name "unconnected-(U4-NC-Pad6)") (class "Default")
      (node (ref "U4") (pin "6") (pinfunction "NC_6") (pintype "passive"))
    )
    (net (code "94") (name "unconnected-(U4-NC-Pad7)") (class "Default")
      (node (ref "U4") (pin "7") (pinfunction "NC_7") (pintype "passive"))
    )
    (net (code "95") (name "unconnected-(U4-NC-Pad14)") (class "Default")
      (node (ref "U4") (pin "14") (pinfunction "NC_14") (pintype "passive"))
    )
    (net (code "96") (name "unconnected-(U5-CSB-Pad2)") (class "Default")
      (node (ref "U5") (pin "2") (pinfunction "CSB_2") (pintype "passive"))
    )
    (net (code "97") (name "unconnected-(U5-SDO-Pad5)") (class "Default")
      (node (ref "U5") (pin "5") (pinfunction "SDO_5") (pintype "passive"))
    )
  )
)
